# mainboard.net
KiCad netlist of a schematic drawn in EAGLE
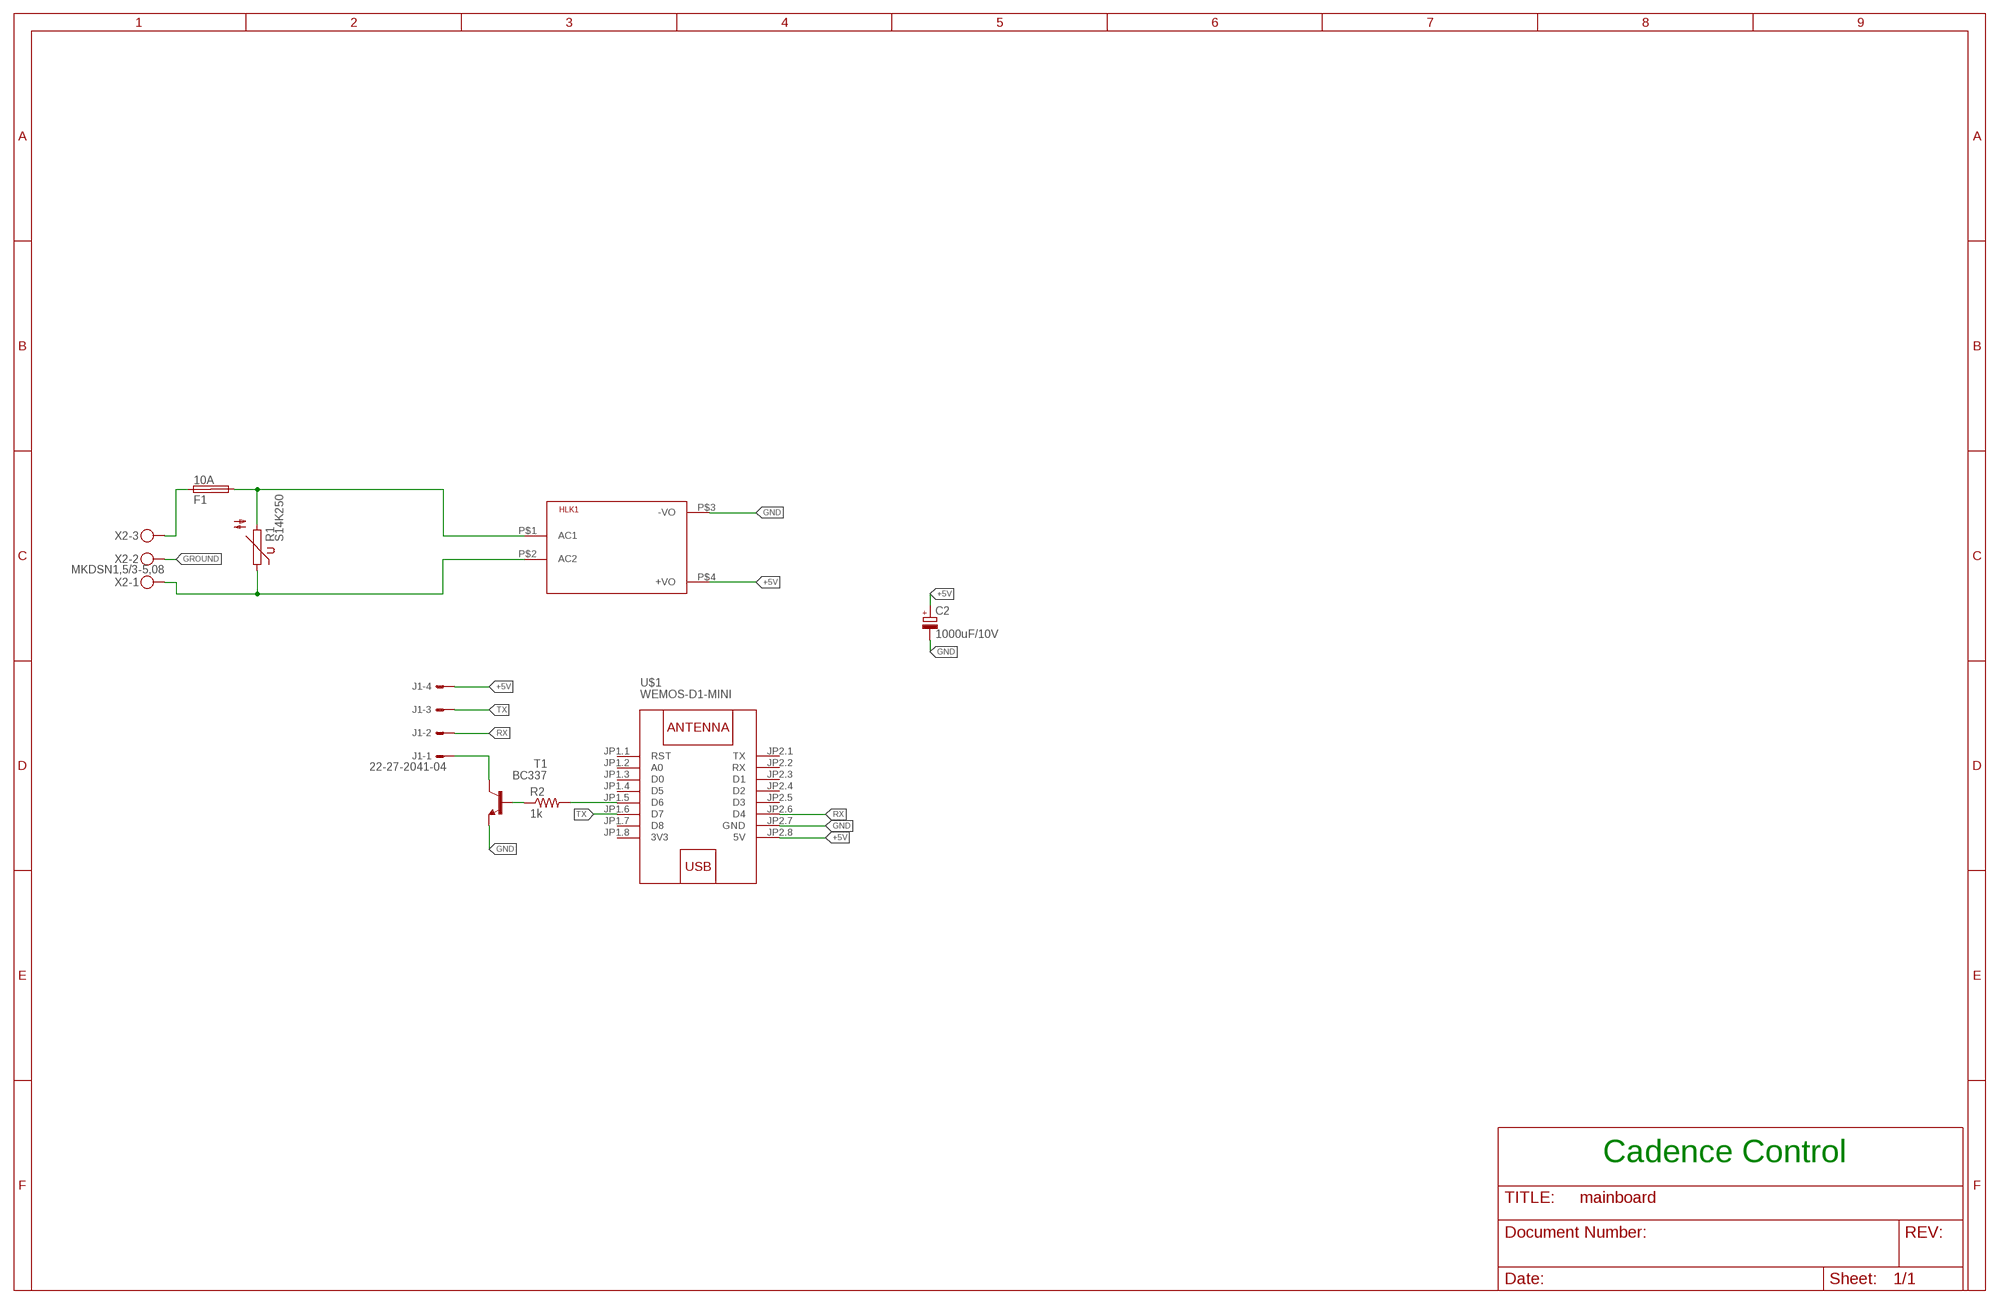
[diagram p0: schematic, sheet 1]

(export (version "E")
  (design (tool "Eeschema 10.0.6"))
  (components
    (comp (ref "C2")
      (value "1000uF/10V")
      (footprint "eagle-import:E3,5-8")
      (libsource (lib "eagle-import") (part "CPOL-EUE3.5-8"))
    )
    (comp (ref "F1")
      (value "10A")
      (footprint "eagle-import:SHK20L")
      (libsource (lib "eagle-import") (part "SHK20L"))
    )
    (comp (ref "HLK1")
      (value "HLK-PM013W")
      (footprint "eagle-import:HLK-PM01")
      (libsource (lib "eagle-import") (part "HLK-PM013W"))
    )
    (comp (ref "J1")
      (value "22-27-2041-04")
      (footprint "eagle-import:6410-04")
      (libsource (lib "eagle-import") (part "22-?-0427-2041"))
    )
    (comp (ref "R1")
      (value "S14K250")
      (footprint "eagle-import:S14K250")
      (libsource (lib "eagle-import") (part "S14K250"))
    )
    (comp (ref "R2")
      (value "1k")
      (footprint "eagle-import:0207_10")
      (libsource (lib "eagle-import") (part "R-US_0207/10"))
    )
    (comp (ref "T1")
      (value "BC337")
      (footprint "eagle-import:TO92")
      (libsource (lib "eagle-import") (part "BC337"))
    )
    (comp (ref "U$1")
      (value "WEMOS-D1-MINI")
      (footprint "eagle-import:WEMOS-D1-MINI")
      (libsource (lib "eagle-import") (part "WEMOS-D1-MINI"))
    )
    (comp (ref "X2")
      (value "MKDSN1,5/3-5,08")
      (footprint "eagle-import:MKDSN1,5_3-5,08")
      (fields (field (name "MPN") "SMKDSN1,5/3-5,08"))
      (libsource (lib "eagle-import") (part "MKDSN1,5/3-5,08"))
    )
  )
  (nets
    (net (code "1") (name "+5V") (class "Default")
      (node (ref "C2") (pin "+") (pinfunction "+_+") (pintype "passive"))
      (node (ref "HLK1") (pin "P$4") (pinfunction "+VO_P$4") (pintype "bidirectional"))
      (node (ref "J1") (pin "4") (pinfunction "S_4") (pintype "passive"))
      (node (ref "U$1") (pin "JP2.8") (pinfunction "5V_JP2.8") (pintype "power_in"))
    )
    (net (code "2") (name "/3V3") (class "Default")
      (node (ref "U$1") (pin "JP1.8") (pinfunction "3V3_JP1.8") (pintype "power_in"))
    )
    (net (code "3") (name "GND") (class "Default")
      (node (ref "C2") (pin "-") (pinfunction "-_-") (pintype "passive"))
      (node (ref "HLK1") (pin "P$3") (pinfunction "-VO_P$3") (pintype "bidirectional"))
      (node (ref "T1") (pin "1") (pinfunction "E_1") (pintype "passive"))
      (node (ref "U$1") (pin "JP2.7") (pinfunction "GND_JP2.7") (pintype "power_in"))
    )
    (net (code "4") (name "GROUND") (class "Default")
      (node (ref "X2") (pin "2") (pinfunction "KL_2") (pintype "passive"))
    )
    (net (code "5") (name "Net-(HLK1-AC1)") (class "Default")
      (node (ref "F1") (pin "2A") (pinfunction "2A_2A") (pintype "passive"))
      (node (ref "HLK1") (pin "P$1") (pinfunction "AC1_P$1") (pintype "bidirectional"))
      (node (ref "R1") (pin "2") (pinfunction "2_2") (pintype "passive"))
    )
    (net (code "6") (name "Net-(HLK1-AC2)") (class "Default")
      (node (ref "HLK1") (pin "P$2") (pinfunction "AC2_P$2") (pintype "bidirectional"))
      (node (ref "R1") (pin "1") (pinfunction "1_1") (pintype "passive"))
      (node (ref "X2") (pin "1") (pinfunction "KL_1") (pintype "passive"))
    )
    (net (code "7") (name "Net-(J1A-S)") (class "Default")
      (node (ref "J1") (pin "1") (pinfunction "S_1") (pintype "passive"))
      (node (ref "T1") (pin "3") (pinfunction "C_3") (pintype "passive"))
    )
    (net (code "8") (name "Net-(T1-B)") (class "Default")
      (node (ref "R2") (pin "1") (pinfunction "1_1") (pintype "passive"))
      (node (ref "T1") (pin "2") (pinfunction "B_2") (pintype "passive"))
    )
    (net (code "9") (name "Net-(U$1-D6)") (class "Default")
      (node (ref "R2") (pin "2") (pinfunction "2_2") (pintype "passive"))
      (node (ref "U$1") (pin "JP1.5") (pinfunction "D6_JP1.5") (pintype "bidirectional"))
    )
    (net (code "10") (name "Net-(X2C-KL)") (class "Default")
      (node (ref "F1") (pin "1A") (pinfunction "1A_1A") (pintype "passive"))
      (node (ref "X2") (pin "3") (pinfunction "KL_3") (pintype "passive"))
    )
    (net (code "11") (name "RX") (class "Default")
      (node (ref "J1") (pin "2") (pinfunction "S_2") (pintype "passive"))
      (node (ref "U$1") (pin "JP2.6") (pinfunction "D4_JP2.6") (pintype "bidirectional"))
    )
    (net (code "12") (name "TX") (class "Default")
      (node (ref "J1") (pin "3") (pinfunction "S_3") (pintype "passive"))
      (node (ref "U$1") (pin "JP1.6") (pinfunction "D7_JP1.6") (pintype "bidirectional"))
    )
    (net (code "13") (name "unconnected-(F1-Pad1B)") (class "Default")
      (node (ref "F1") (pin "1B") (pinfunction "1B_1B") (pintype "passive"))
    )
    (net (code "14") (name "unconnected-(F1-Pad2B)") (class "Default")
      (node (ref "F1") (pin "2B") (pinfunction "2B_2B") (pintype "passive"))
    )
    (net (code "15") (name "unconnected-(U$1-A0-PadJP1.2)") (class "Default")
      (node (ref "U$1") (pin "JP1.2") (pinfunction "A0_JP1.2") (pintype "bidirectional"))
    )
    (net (code "16") (name "unconnected-(U$1-D0-PadJP1.3)") (class "Default")
      (node (ref "U$1") (pin "JP1.3") (pinfunction "D0_JP1.3") (pintype "bidirectional"))
    )
    (net (code "17") (name "unconnected-(U$1-D1-PadJP2.3)") (class "Default")
      (node (ref "U$1") (pin "JP2.3") (pinfunction "D1_JP2.3") (pintype "bidirectional"))
    )
    (net (code "18") (name "unconnected-(U$1-D2-PadJP2.4)") (class "Default")
      (node (ref "U$1") (pin "JP2.4") (pinfunction "D2_JP2.4") (pintype "bidirectional"))
    )
    (net (code "19") (name "unconnected-(U$1-D3-PadJP2.5)") (class "Default")
      (node (ref "U$1") (pin "JP2.5") (pinfunction "D3_JP2.5") (pintype "bidirectional"))
    )
    (net (code "20") (name "unconnected-(U$1-D5-PadJP1.4)") (class "Default")
      (node (ref "U$1") (pin "JP1.4") (pinfunction "D5_JP1.4") (pintype "bidirectional"))
    )
    (net (code "21") (name "unconnected-(U$1-D8-PadJP1.7)") (class "Default")
      (node (ref "U$1") (pin "JP1.7") (pinfunction "D8_JP1.7") (pintype "bidirectional"))
    )
    (net (code "22") (name "unconnected-(U$1-RST-PadJP1.1)") (class "Default")
      (node (ref "U$1") (pin "JP1.1") (pinfunction "RST_JP1.1") (pintype "bidirectional"))
    )
    (net (code "23") (name "unconnected-(U$1-RX-PadJP2.2)") (class "Default")
      (node (ref "U$1") (pin "JP2.2") (pinfunction "RX_JP2.2") (pintype "bidirectional"))
    )
    (net (code "24") (name "unconnected-(U$1-TX-PadJP2.1)") (class "Default")
      (node (ref "U$1") (pin "JP2.1") (pinfunction "TX_JP2.1") (pintype "bidirectional"))
    )
  )
)
